# RPi_SPI_outputs_v02.net
KiCad netlist of a schematic drawn in EAGLE
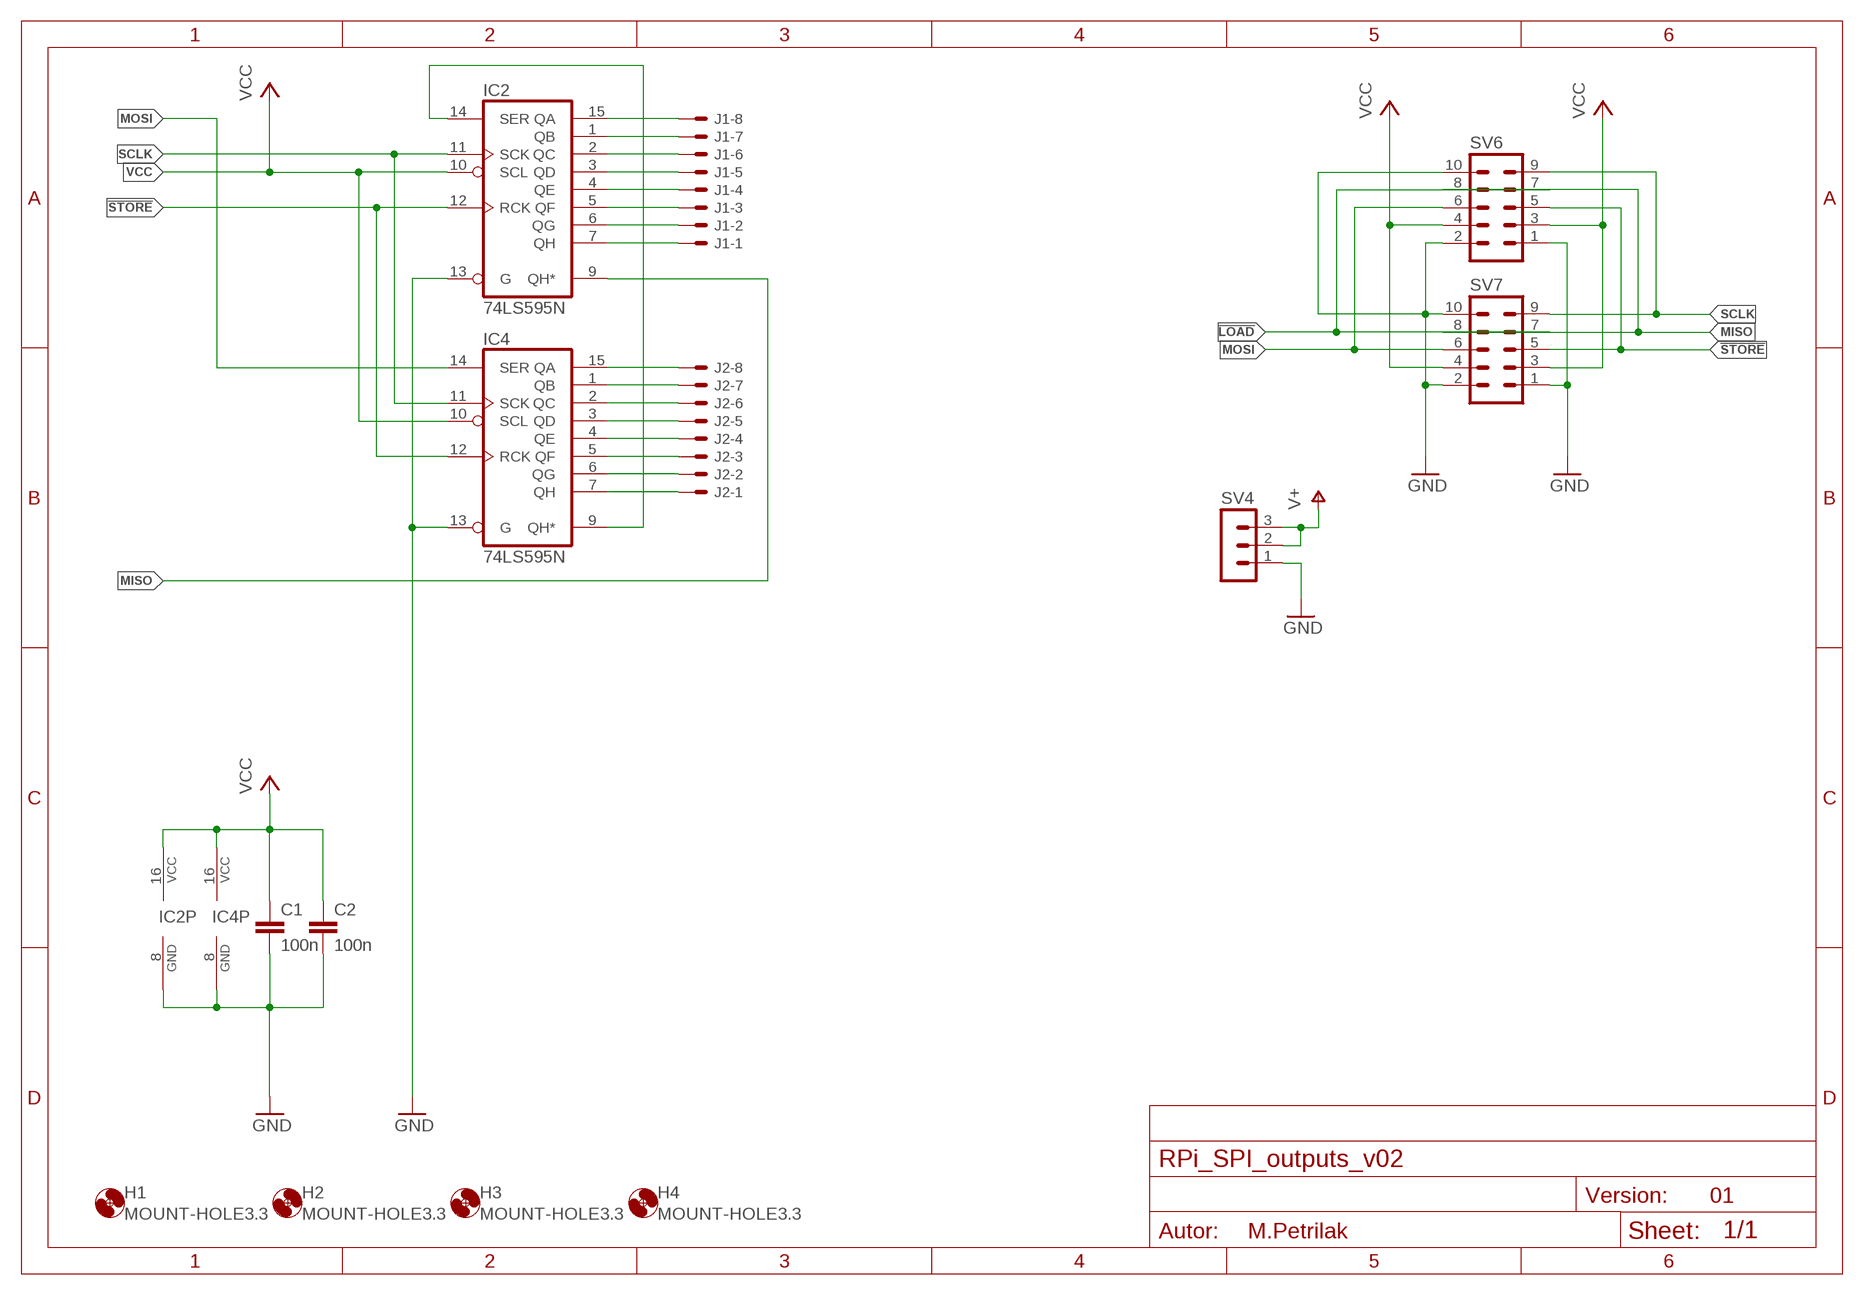
[diagram p0: schematic, sheet 1]

(export (version "E")
  (design (tool "Eeschema 10.0.6"))
  (components
    (comp (ref "C1")
      (value "100n")
      (footprint "eagle-import:C1206")
      (libsource (lib "eagle-import") (part "C-EUC1206"))
    )
    (comp (ref "C2")
      (value "100n")
      (footprint "eagle-import:C1206")
      (libsource (lib "eagle-import") (part "C-EUC1206"))
    )
    (comp (ref "H1")
      (value "MOUNT-HOLE3.3")
      (footprint "eagle-import:3,3")
      (libsource (lib "eagle-import") (part "MOUNT-HOLE3.3"))
    )
    (comp (ref "H2")
      (value "MOUNT-HOLE3.3")
      (footprint "eagle-import:3,3")
      (libsource (lib "eagle-import") (part "MOUNT-HOLE3.3"))
    )
    (comp (ref "H3")
      (value "MOUNT-HOLE3.3")
      (footprint "eagle-import:3,3")
      (libsource (lib "eagle-import") (part "MOUNT-HOLE3.3"))
    )
    (comp (ref "H4")
      (value "MOUNT-HOLE3.3")
      (footprint "eagle-import:3,3")
      (libsource (lib "eagle-import") (part "MOUNT-HOLE3.3"))
    )
    (comp (ref "IC2")
      (value "74LS595N")
      (footprint "eagle-import:DIL16")
      (libsource (lib "eagle-import") (part "74595NLS"))
    )
    (comp (ref "IC4")
      (value "74LS595N")
      (footprint "eagle-import:DIL16")
      (libsource (lib "eagle-import") (part "74595NLS"))
    )
    (comp (ref "J1")
      (value "22-05-7088-SPEC-08")
      (footprint "eagle-import:7395-08_SPEC")
      (libsource (lib "eagle-import") (part "22-?-0805-7088-SPEC"))
    )
    (comp (ref "J2")
      (value "22-05-7088-SPEC-08")
      (footprint "eagle-import:7395-08_SPEC")
      (libsource (lib "eagle-import") (part "22-?-0805-7088-SPEC"))
    )
    (comp (ref "SV4")
      (value "MA03-1_NO")
      (footprint "eagle-import:MA03-1_NO")
      (libsource (lib "eagle-import") (part "MA03-1_NO"))
    )
    (comp (ref "SV6")
      (value "ML10")
      (footprint "eagle-import:ML10")
      (libsource (lib "eagle-import") (part "ML10"))
    )
    (comp (ref "SV7")
      (value "ML10")
      (footprint "eagle-import:ML10")
      (libsource (lib "eagle-import") (part "ML10"))
    )
  )
  (nets
    (net (code "1") (name "/~{LOAD}") (class "Default")
      (node (ref "SV6") (pin "7") (pinfunction "7_7") (pintype "passive"))
      (node (ref "SV7") (pin "7") (pinfunction "7_7") (pintype "passive"))
    )
    (net (code "2") (name "/~{STORE}") (class "Default")
      (node (ref "IC2") (pin "12") (pinfunction "RCK_12") (pintype "input"))
      (node (ref "IC4") (pin "12") (pinfunction "RCK_12") (pintype "input"))
      (node (ref "SV6") (pin "5") (pinfunction "5_5") (pintype "passive"))
      (node (ref "SV7") (pin "5") (pinfunction "5_5") (pintype "passive"))
    )
    (net (code "3") (name "GND") (class "Default")
      (node (ref "C1") (pin "2") (pinfunction "2_2") (pintype "passive"))
      (node (ref "C2") (pin "2") (pinfunction "2_2") (pintype "passive"))
      (node (ref "IC2") (pin "13") (pinfunction "G_13") (pintype "input"))
      (node (ref "IC2") (pin "8") (pinfunction "GND_8") (pintype "power_in"))
      (node (ref "IC4") (pin "13") (pinfunction "G_13") (pintype "input"))
      (node (ref "IC4") (pin "8") (pinfunction "GND_8") (pintype "power_in"))
      (node (ref "SV4") (pin "1") (pinfunction "1_1") (pintype "passive"))
      (node (ref "SV6") (pin "1") (pinfunction "1_1") (pintype "passive"))
      (node (ref "SV6") (pin "10") (pinfunction "10_10") (pintype "passive"))
      (node (ref "SV6") (pin "2") (pinfunction "2_2") (pintype "passive"))
      (node (ref "SV7") (pin "1") (pinfunction "1_1") (pintype "passive"))
      (node (ref "SV7") (pin "10") (pinfunction "10_10") (pintype "passive"))
      (node (ref "SV7") (pin "2") (pinfunction "2_2") (pintype "passive"))
    )
    (net (code "4") (name "MISO") (class "Default")
      (node (ref "IC2") (pin "9") (pinfunction "QH*_9") (pintype "tri_state"))
      (node (ref "SV6") (pin "8") (pinfunction "8_8") (pintype "passive"))
      (node (ref "SV7") (pin "8") (pinfunction "8_8") (pintype "passive"))
    )
    (net (code "5") (name "MOSI") (class "Default")
      (node (ref "IC4") (pin "14") (pinfunction "SER_14") (pintype "input"))
      (node (ref "SV6") (pin "6") (pinfunction "6_6") (pintype "passive"))
      (node (ref "SV7") (pin "6") (pinfunction "6_6") (pintype "passive"))
    )
    (net (code "6") (name "Net-(IC2A-QA)") (class "Default")
      (node (ref "IC2") (pin "15") (pinfunction "QA_15") (pintype "tri_state"))
      (node (ref "J1") (pin "8") (pinfunction "S_8") (pintype "passive"))
    )
    (net (code "7") (name "Net-(IC2A-QB)") (class "Default")
      (node (ref "IC2") (pin "1") (pinfunction "QB_1") (pintype "tri_state"))
      (node (ref "J1") (pin "7") (pinfunction "S_7") (pintype "passive"))
    )
    (net (code "8") (name "Net-(IC2A-QC)") (class "Default")
      (node (ref "IC2") (pin "2") (pinfunction "QC_2") (pintype "tri_state"))
      (node (ref "J1") (pin "6") (pinfunction "S_6") (pintype "passive"))
    )
    (net (code "9") (name "Net-(IC2A-QD)") (class "Default")
      (node (ref "IC2") (pin "3") (pinfunction "QD_3") (pintype "tri_state"))
      (node (ref "J1") (pin "5") (pinfunction "S_5") (pintype "passive"))
    )
    (net (code "10") (name "Net-(IC2A-QE)") (class "Default")
      (node (ref "IC2") (pin "4") (pinfunction "QE_4") (pintype "tri_state"))
      (node (ref "J1") (pin "4") (pinfunction "S_4") (pintype "passive"))
    )
    (net (code "11") (name "Net-(IC2A-QF)") (class "Default")
      (node (ref "IC2") (pin "5") (pinfunction "QF_5") (pintype "tri_state"))
      (node (ref "J1") (pin "3") (pinfunction "S_3") (pintype "passive"))
    )
    (net (code "12") (name "Net-(IC2A-QG)") (class "Default")
      (node (ref "IC2") (pin "6") (pinfunction "QG_6") (pintype "tri_state"))
      (node (ref "J1") (pin "2") (pinfunction "S_2") (pintype "passive"))
    )
    (net (code "13") (name "Net-(IC2A-QH)") (class "Default")
      (node (ref "IC2") (pin "7") (pinfunction "QH_7") (pintype "tri_state"))
      (node (ref "J1") (pin "1") (pinfunction "S_1") (pintype "passive"))
    )
    (net (code "14") (name "Net-(IC2A-SER)") (class "Default")
      (node (ref "IC2") (pin "14") (pinfunction "SER_14") (pintype "input"))
      (node (ref "IC4") (pin "9") (pinfunction "QH*_9") (pintype "tri_state"))
    )
    (net (code "15") (name "Net-(IC4A-QA)") (class "Default")
      (node (ref "IC4") (pin "15") (pinfunction "QA_15") (pintype "tri_state"))
      (node (ref "J2") (pin "8") (pinfunction "S_8") (pintype "passive"))
    )
    (net (code "16") (name "Net-(IC4A-QB)") (class "Default")
      (node (ref "IC4") (pin "1") (pinfunction "QB_1") (pintype "tri_state"))
      (node (ref "J2") (pin "7") (pinfunction "S_7") (pintype "passive"))
    )
    (net (code "17") (name "Net-(IC4A-QC)") (class "Default")
      (node (ref "IC4") (pin "2") (pinfunction "QC_2") (pintype "tri_state"))
      (node (ref "J2") (pin "6") (pinfunction "S_6") (pintype "passive"))
    )
    (net (code "18") (name "Net-(IC4A-QD)") (class "Default")
      (node (ref "IC4") (pin "3") (pinfunction "QD_3") (pintype "tri_state"))
      (node (ref "J2") (pin "5") (pinfunction "S_5") (pintype "passive"))
    )
    (net (code "19") (name "Net-(IC4A-QE)") (class "Default")
      (node (ref "IC4") (pin "4") (pinfunction "QE_4") (pintype "tri_state"))
      (node (ref "J2") (pin "4") (pinfunction "S_4") (pintype "passive"))
    )
    (net (code "20") (name "Net-(IC4A-QF)") (class "Default")
      (node (ref "IC4") (pin "5") (pinfunction "QF_5") (pintype "tri_state"))
      (node (ref "J2") (pin "3") (pinfunction "S_3") (pintype "passive"))
    )
    (net (code "21") (name "Net-(IC4A-QG)") (class "Default")
      (node (ref "IC4") (pin "6") (pinfunction "QG_6") (pintype "tri_state"))
      (node (ref "J2") (pin "2") (pinfunction "S_2") (pintype "passive"))
    )
    (net (code "22") (name "Net-(IC4A-QH)") (class "Default")
      (node (ref "IC4") (pin "7") (pinfunction "QH_7") (pintype "tri_state"))
      (node (ref "J2") (pin "1") (pinfunction "S_1") (pintype "passive"))
    )
    (net (code "23") (name "SCLK") (class "Default")
      (node (ref "IC2") (pin "11") (pinfunction "SCK_11") (pintype "input"))
      (node (ref "IC4") (pin "11") (pinfunction "SCK_11") (pintype "input"))
      (node (ref "SV6") (pin "9") (pinfunction "9_9") (pintype "passive"))
      (node (ref "SV7") (pin "9") (pinfunction "9_9") (pintype "passive"))
    )
    (net (code "24") (name "V+") (class "Default")
      (node (ref "SV4") (pin "2") (pinfunction "2_2") (pintype "passive"))
      (node (ref "SV4") (pin "3") (pinfunction "3_3") (pintype "passive"))
    )
    (net (code "25") (name "VCC") (class "Default")
      (node (ref "C1") (pin "1") (pinfunction "1_1") (pintype "passive"))
      (node (ref "C2") (pin "1") (pinfunction "1_1") (pintype "passive"))
      (node (ref "IC2") (pin "10") (pinfunction "SCL_10") (pintype "input"))
      (node (ref "IC2") (pin "16") (pinfunction "VCC_16") (pintype "power_in"))
      (node (ref "IC4") (pin "10") (pinfunction "SCL_10") (pintype "input"))
      (node (ref "IC4") (pin "16") (pinfunction "VCC_16") (pintype "power_in"))
      (node (ref "SV6") (pin "3") (pinfunction "3_3") (pintype "passive"))
      (node (ref "SV6") (pin "4") (pinfunction "4_4") (pintype "passive"))
      (node (ref "SV7") (pin "3") (pinfunction "3_3") (pintype "passive"))
      (node (ref "SV7") (pin "4") (pinfunction "4_4") (pintype "passive"))
    )
  )
)
